# TimerShield.net
KiCad netlist of a schematic drawn in EAGLE
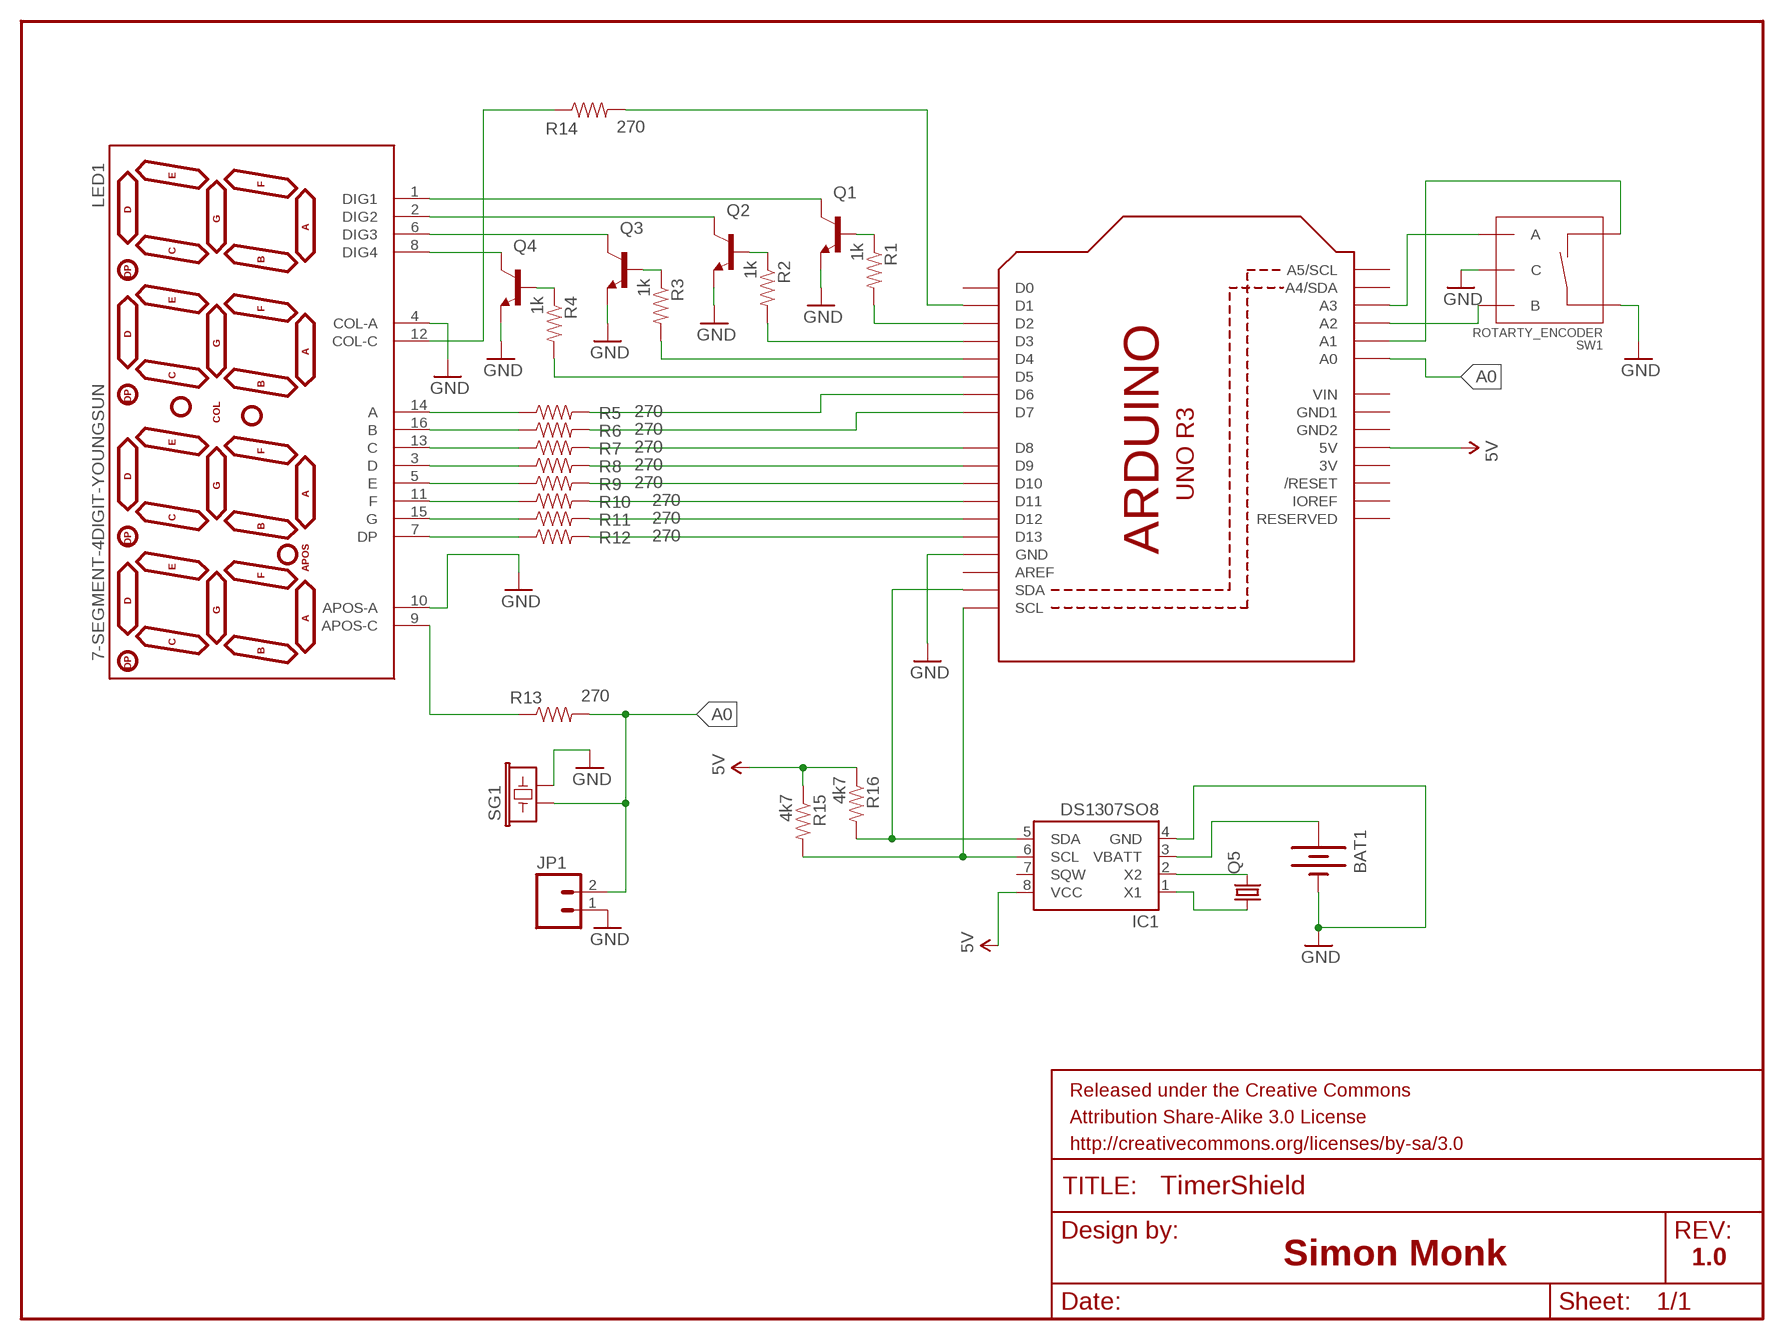
[diagram p0: schematic, sheet 1]

(export (version "E")
  (design (tool "Eeschema 10.0.6"))
  (components
    (comp (ref "BAT1")
      (value "BATTERY12MM")
      (footprint "eagle-import:BATTCON_12MM")
      (libsource (lib "eagle-import") (part "BATTERY12MM"))
    )
    (comp (ref "FRAME1")
      (value "FRAME-LETTER")
      (footprint "eagle-import:CREATIVE_COMMONS")
      (libsource (lib "eagle-import") (part "FRAME-LETTER"))
    )
    (comp (ref "IC1")
      (value "DS1307SO8")
      (footprint "eagle-import:SO08")
      (libsource (lib "eagle-import") (part "DS1307SO8"))
    )
    (comp (ref "JP1")
      (value "M023.5MM")
      (footprint "eagle-import:SCREWTERMINAL-3.5MM-2")
      (libsource (lib "eagle-import") (part "M023.5MM"))
    )
    (comp (ref "LED1")
      (value "7-SEGMENT-4DIGIT-YOUNGSUN")
      (footprint "eagle-import:7-SEGMENT-4DIGIT-YOUNGSUN")
      (libsource (lib "eagle-import") (part "7-SEGMENT-4DIGIT-YOUNGSUN"))
    )
    (comp (ref "Q1")
      (value "TRANSISTOR_NPNSOT23")
      (footprint "eagle-import:SOT23")
      (libsource (lib "eagle-import") (part "TRANSISTOR_NPNSOT23"))
    )
    (comp (ref "Q2")
      (value "TRANSISTOR_NPNSOT23")
      (footprint "eagle-import:SOT23")
      (libsource (lib "eagle-import") (part "TRANSISTOR_NPNSOT23"))
    )
    (comp (ref "Q3")
      (value "TRANSISTOR_NPNSOT23")
      (footprint "eagle-import:SOT23")
      (libsource (lib "eagle-import") (part "TRANSISTOR_NPNSOT23"))
    )
    (comp (ref "Q4")
      (value "TRANSISTOR_NPNSOT23")
      (footprint "eagle-import:SOT23")
      (libsource (lib "eagle-import") (part "TRANSISTOR_NPNSOT23"))
    )
    (comp (ref "Q5")
      (value "CRYSTALTC26H")
      (footprint "eagle-import:TC26H")
      (libsource (lib "eagle-import") (part "CRYSTALTC26H"))
    )
    (comp (ref "R1")
      (value "1k")
      (footprint "eagle-import:0805")
      (libsource (lib "eagle-import") (part "RESISTOR0805-RES"))
    )
    (comp (ref "R2")
      (value "1k")
      (footprint "eagle-import:0805")
      (libsource (lib "eagle-import") (part "RESISTOR0805-RES"))
    )
    (comp (ref "R3")
      (value "1k")
      (footprint "eagle-import:0805")
      (libsource (lib "eagle-import") (part "RESISTOR0805-RES"))
    )
    (comp (ref "R4")
      (value "1k")
      (footprint "eagle-import:0805")
      (libsource (lib "eagle-import") (part "RESISTOR0805-RES"))
    )
    (comp (ref "R5")
      (value "270")
      (footprint "eagle-import:0805")
      (libsource (lib "eagle-import") (part "RESISTOR0805-RES"))
    )
    (comp (ref "R6")
      (value "270")
      (footprint "eagle-import:0805")
      (libsource (lib "eagle-import") (part "RESISTOR0805-RES"))
    )
    (comp (ref "R7")
      (value "270")
      (footprint "eagle-import:0805")
      (libsource (lib "eagle-import") (part "RESISTOR0805-RES"))
    )
    (comp (ref "R8")
      (value "270")
      (footprint "eagle-import:0805")
      (libsource (lib "eagle-import") (part "RESISTOR0805-RES"))
    )
    (comp (ref "R9")
      (value "270")
      (footprint "eagle-import:0805")
      (libsource (lib "eagle-import") (part "RESISTOR0805-RES"))
    )
    (comp (ref "R10")
      (value "270")
      (footprint "eagle-import:0805")
      (libsource (lib "eagle-import") (part "RESISTOR0805-RES"))
    )
    (comp (ref "R11")
      (value "270")
      (footprint "eagle-import:0805")
      (libsource (lib "eagle-import") (part "RESISTOR0805-RES"))
    )
    (comp (ref "R12")
      (value "270")
      (footprint "eagle-import:0805")
      (libsource (lib "eagle-import") (part "RESISTOR0805-RES"))
    )
    (comp (ref "R13")
      (value "270")
      (footprint "eagle-import:0805")
      (libsource (lib "eagle-import") (part "RESISTOR0805-RES"))
    )
    (comp (ref "R14")
      (value "270")
      (footprint "eagle-import:0805")
      (libsource (lib "eagle-import") (part "RESISTOR0805-RES"))
    )
    (comp (ref "R15")
      (value "4k7")
      (footprint "eagle-import:0805")
      (libsource (lib "eagle-import") (part "RESISTOR0805-RES"))
    )
    (comp (ref "R16")
      (value "4k7")
      (footprint "eagle-import:0805")
      (libsource (lib "eagle-import") (part "RESISTOR0805-RES"))
    )
    (comp (ref "SG1")
      (value "BUZZERNS")
      (footprint "eagle-import:BUZZER-12MM-NS")
      (libsource (lib "eagle-import") (part "BUZZERNS"))
    )
    (comp (ref "SW1")
      (value "ROTARTY_ENCODER")
      (footprint "eagle-import:ROTARY_ENC_PLAIN")
      (libsource (lib "eagle-import") (part "ROTARTY_ENCODER"))
    )
    (comp (ref "U1")
      (value "ARDUINOR3-DIMENSION")
      (footprint "eagle-import:ARDUINOR3")
      (libsource (lib "eagle-import") (part "ARDUINOR3-DIMENSION"))
    )
  )
  (nets
    (net (code "1") (name "/3V") (class "Default")
      (node (ref "U1") (pin "3V") (pinfunction "3V_3V") (pintype "power_in"))
    )
    (net (code "2") (name "/GND1") (class "Default")
      (node (ref "U1") (pin "GND1") (pinfunction "GND1_GND1") (pintype "power_in"))
    )
    (net (code "3") (name "/GND2") (class "Default")
      (node (ref "U1") (pin "GND2") (pinfunction "GND2_GND2") (pintype "power_in"))
    )
    (net (code "4") (name "/VIN") (class "Default")
      (node (ref "U1") (pin "VIN") (pinfunction "VIN_VIN") (pintype "power_in"))
    )
    (net (code "5") (name "5V") (class "Default")
      (node (ref "IC1") (pin "8") (pinfunction "VCC_8") (pintype "bidirectional"))
      (node (ref "R15") (pin "1") (pinfunction "1_1") (pintype "passive"))
      (node (ref "R16") (pin "1") (pinfunction "1_1") (pintype "passive"))
      (node (ref "U1") (pin "5V") (pinfunction "5V_5V") (pintype "power_in"))
    )
    (net (code "6") (name "A0") (class "Default")
      (node (ref "JP1") (pin "2") (pinfunction "2_2") (pintype "passive"))
      (node (ref "R13") (pin "2") (pinfunction "2_2") (pintype "passive"))
      (node (ref "SG1") (pin "+") (pinfunction "1_+") (pintype "passive"))
      (node (ref "U1") (pin "A0") (pinfunction "A0_A0") (pintype "bidirectional"))
    )
    (net (code "7") (name "GND") (class "Default")
      (node (ref "BAT1") (pin "GND") (pinfunction "-_GND") (pintype "power_in"))
      (node (ref "IC1") (pin "4") (pinfunction "GND_4") (pintype "bidirectional"))
      (node (ref "JP1") (pin "1") (pinfunction "1_1") (pintype "passive"))
      (node (ref "LED1") (pin "10") (pinfunction "APOS-A_10") (pintype "bidirectional"))
      (node (ref "LED1") (pin "4") (pinfunction "COL-A_4") (pintype "bidirectional"))
      (node (ref "Q1") (pin "2") (pinfunction "E_2") (pintype "passive"))
      (node (ref "Q2") (pin "2") (pinfunction "E_2") (pintype "passive"))
      (node (ref "Q3") (pin "2") (pinfunction "E_2") (pintype "passive"))
      (node (ref "Q4") (pin "2") (pinfunction "E_2") (pintype "passive"))
      (node (ref "SG1") (pin "-") (pinfunction "2_-") (pintype "passive"))
      (node (ref "SW1") (pin "C") (pinfunction "C_C") (pintype "bidirectional"))
      (node (ref "SW1") (pin "SW+") (pinfunction "SW+_SW+") (pintype "bidirectional"))
      (node (ref "U1") (pin "GND") (pinfunction "GND_GND") (pintype "power_in"))
    )
    (net (code "8") (name "Net-(BAT1-+)") (class "Default")
      (node (ref "BAT1") (pin "PWR@1") (pinfunction "+_PWR@1") (pintype "power_in"))
      (node (ref "IC1") (pin "3") (pinfunction "VBATT_3") (pintype "bidirectional"))
    )
    (net (code "9") (name "Net-(IC1-SCL)") (class "Default")
      (node (ref "IC1") (pin "6") (pinfunction "SCL_6") (pintype "bidirectional"))
      (node (ref "R15") (pin "2") (pinfunction "2_2") (pintype "passive"))
      (node (ref "U1") (pin "SCL") (pinfunction "SCL_SCL") (pintype "bidirectional"))
    )
    (net (code "10") (name "Net-(IC1-SDA)") (class "Default")
      (node (ref "IC1") (pin "5") (pinfunction "SDA_5") (pintype "bidirectional"))
      (node (ref "R16") (pin "2") (pinfunction "2_2") (pintype "passive"))
      (node (ref "U1") (pin "SDA") (pinfunction "SDA_SDA") (pintype "bidirectional"))
    )
    (net (code "11") (name "Net-(IC1-X1)") (class "Default")
      (node (ref "IC1") (pin "1") (pinfunction "X1_1") (pintype "bidirectional"))
      (node (ref "Q5") (pin "1") (pinfunction "1_1") (pintype "passive"))
    )
    (net (code "12") (name "Net-(IC1-X2)") (class "Default")
      (node (ref "IC1") (pin "2") (pinfunction "X2_2") (pintype "bidirectional"))
      (node (ref "Q5") (pin "2") (pinfunction "2_2") (pintype "passive"))
    )
    (net (code "13") (name "Net-(LED1-A)") (class "Default")
      (node (ref "LED1") (pin "14") (pinfunction "A_14") (pintype "bidirectional"))
      (node (ref "R5") (pin "1") (pinfunction "1_1") (pintype "passive"))
    )
    (net (code "14") (name "Net-(LED1-APOS-C)") (class "Default")
      (node (ref "LED1") (pin "9") (pinfunction "APOS-C_9") (pintype "bidirectional"))
      (node (ref "R13") (pin "1") (pinfunction "1_1") (pintype "passive"))
    )
    (net (code "15") (name "Net-(LED1-B)") (class "Default")
      (node (ref "LED1") (pin "16") (pinfunction "B_16") (pintype "bidirectional"))
      (node (ref "R6") (pin "1") (pinfunction "1_1") (pintype "passive"))
    )
    (net (code "16") (name "Net-(LED1-C)") (class "Default")
      (node (ref "LED1") (pin "13") (pinfunction "C_13") (pintype "bidirectional"))
      (node (ref "R7") (pin "1") (pinfunction "1_1") (pintype "passive"))
    )
    (net (code "17") (name "Net-(LED1-COL-C)") (class "Default")
      (node (ref "LED1") (pin "12") (pinfunction "COL-C_12") (pintype "bidirectional"))
      (node (ref "R14") (pin "1") (pinfunction "1_1") (pintype "passive"))
    )
    (net (code "18") (name "Net-(LED1-D)") (class "Default")
      (node (ref "LED1") (pin "3") (pinfunction "D_3") (pintype "bidirectional"))
      (node (ref "R8") (pin "1") (pinfunction "1_1") (pintype "passive"))
    )
    (net (code "19") (name "Net-(LED1-DIG1)") (class "Default")
      (node (ref "LED1") (pin "1") (pinfunction "DIG1_1") (pintype "bidirectional"))
      (node (ref "Q1") (pin "3") (pinfunction "C_3") (pintype "passive"))
    )
    (net (code "20") (name "Net-(LED1-DIG2)") (class "Default")
      (node (ref "LED1") (pin "2") (pinfunction "DIG2_2") (pintype "bidirectional"))
      (node (ref "Q2") (pin "3") (pinfunction "C_3") (pintype "passive"))
    )
    (net (code "21") (name "Net-(LED1-DIG3)") (class "Default")
      (node (ref "LED1") (pin "6") (pinfunction "DIG3_6") (pintype "bidirectional"))
      (node (ref "Q3") (pin "3") (pinfunction "C_3") (pintype "passive"))
    )
    (net (code "22") (name "Net-(LED1-DIG4)") (class "Default")
      (node (ref "LED1") (pin "8") (pinfunction "DIG4_8") (pintype "bidirectional"))
      (node (ref "Q4") (pin "3") (pinfunction "C_3") (pintype "passive"))
    )
    (net (code "23") (name "Net-(LED1-DP)") (class "Default")
      (node (ref "LED1") (pin "7") (pinfunction "DP_7") (pintype "bidirectional"))
      (node (ref "R12") (pin "1") (pinfunction "1_1") (pintype "passive"))
    )
    (net (code "24") (name "Net-(LED1-E)") (class "Default")
      (node (ref "LED1") (pin "5") (pinfunction "E_5") (pintype "bidirectional"))
      (node (ref "R9") (pin "1") (pinfunction "1_1") (pintype "passive"))
    )
    (net (code "25") (name "Net-(LED1-F)") (class "Default")
      (node (ref "LED1") (pin "11") (pinfunction "F_11") (pintype "bidirectional"))
      (node (ref "R10") (pin "1") (pinfunction "1_1") (pintype "passive"))
    )
    (net (code "26") (name "Net-(LED1-G)") (class "Default")
      (node (ref "LED1") (pin "15") (pinfunction "G_15") (pintype "bidirectional"))
      (node (ref "R11") (pin "1") (pinfunction "1_1") (pintype "passive"))
    )
    (net (code "27") (name "Net-(Q1-B)") (class "Default")
      (node (ref "Q1") (pin "1") (pinfunction "B_1") (pintype "passive"))
      (node (ref "R1") (pin "1") (pinfunction "1_1") (pintype "passive"))
    )
    (net (code "28") (name "Net-(Q2-B)") (class "Default")
      (node (ref "Q2") (pin "1") (pinfunction "B_1") (pintype "passive"))
      (node (ref "R2") (pin "1") (pinfunction "1_1") (pintype "passive"))
    )
    (net (code "29") (name "Net-(Q3-B)") (class "Default")
      (node (ref "Q3") (pin "1") (pinfunction "B_1") (pintype "passive"))
      (node (ref "R3") (pin "1") (pinfunction "1_1") (pintype "passive"))
    )
    (net (code "30") (name "Net-(Q4-B)") (class "Default")
      (node (ref "Q4") (pin "1") (pinfunction "B_1") (pintype "passive"))
      (node (ref "R4") (pin "1") (pinfunction "1_1") (pintype "passive"))
    )
    (net (code "31") (name "Net-(R1-Pad2)") (class "Default")
      (node (ref "R1") (pin "2") (pinfunction "2_2") (pintype "passive"))
      (node (ref "U1") (pin "D2") (pinfunction "D2_D2") (pintype "bidirectional"))
    )
    (net (code "32") (name "Net-(R2-Pad2)") (class "Default")
      (node (ref "R2") (pin "2") (pinfunction "2_2") (pintype "passive"))
      (node (ref "U1") (pin "D3") (pinfunction "D3_D3") (pintype "bidirectional"))
    )
    (net (code "33") (name "Net-(R3-Pad2)") (class "Default")
      (node (ref "R3") (pin "2") (pinfunction "2_2") (pintype "passive"))
      (node (ref "U1") (pin "D4") (pinfunction "D4_D4") (pintype "bidirectional"))
    )
    (net (code "34") (name "Net-(R4-Pad2)") (class "Default")
      (node (ref "R4") (pin "2") (pinfunction "2_2") (pintype "passive"))
      (node (ref "U1") (pin "D5") (pinfunction "D5_D5") (pintype "bidirectional"))
    )
    (net (code "35") (name "Net-(R5-Pad2)") (class "Default")
      (node (ref "R5") (pin "2") (pinfunction "2_2") (pintype "passive"))
      (node (ref "U1") (pin "D6") (pinfunction "D6_D6") (pintype "bidirectional"))
    )
    (net (code "36") (name "Net-(R6-Pad2)") (class "Default")
      (node (ref "R6") (pin "2") (pinfunction "2_2") (pintype "passive"))
      (node (ref "U1") (pin "D7") (pinfunction "D7_D7") (pintype "bidirectional"))
    )
    (net (code "37") (name "Net-(R7-Pad2)") (class "Default")
      (node (ref "R7") (pin "2") (pinfunction "2_2") (pintype "passive"))
      (node (ref "U1") (pin "D8") (pinfunction "D8_D8") (pintype "bidirectional"))
    )
    (net (code "38") (name "Net-(R8-Pad2)") (class "Default")
      (node (ref "R8") (pin "2") (pinfunction "2_2") (pintype "passive"))
      (node (ref "U1") (pin "D9") (pinfunction "D9_D9") (pintype "bidirectional"))
    )
    (net (code "39") (name "Net-(R9-Pad2)") (class "Default")
      (node (ref "R9") (pin "2") (pinfunction "2_2") (pintype "passive"))
      (node (ref "U1") (pin "D10") (pinfunction "D10_D10") (pintype "bidirectional"))
    )
    (net (code "40") (name "Net-(R10-Pad2)") (class "Default")
      (node (ref "R10") (pin "2") (pinfunction "2_2") (pintype "passive"))
      (node (ref "U1") (pin "D11") (pinfunction "D11_D11") (pintype "bidirectional"))
    )
    (net (code "41") (name "Net-(R11-Pad2)") (class "Default")
      (node (ref "R11") (pin "2") (pinfunction "2_2") (pintype "passive"))
      (node (ref "U1") (pin "D12") (pinfunction "D12_D12") (pintype "bidirectional"))
    )
    (net (code "42") (name "Net-(R12-Pad2)") (class "Default")
      (node (ref "R12") (pin "2") (pinfunction "2_2") (pintype "passive"))
      (node (ref "U1") (pin "D13") (pinfunction "D13_D13") (pintype "bidirectional"))
    )
    (net (code "43") (name "Net-(R14-Pad2)") (class "Default")
      (node (ref "R14") (pin "2") (pinfunction "2_2") (pintype "passive"))
      (node (ref "U1") (pin "D1") (pinfunction "D1_D1") (pintype "bidirectional"))
    )
    (net (code "44") (name "Net-(SW1-PadA)") (class "Default")
      (node (ref "SW1") (pin "A") (pinfunction "A_A") (pintype "bidirectional"))
      (node (ref "U1") (pin "A3") (pinfunction "A3_A3") (pintype "bidirectional"))
    )
    (net (code "45") (name "Net-(SW1-PadB)") (class "Default")
      (node (ref "SW1") (pin "B") (pinfunction "B_B") (pintype "bidirectional"))
      (node (ref "U1") (pin "A2") (pinfunction "A2_A2") (pintype "bidirectional"))
    )
    (net (code "46") (name "Net-(SW1-PadSW-)") (class "Default")
      (node (ref "SW1") (pin "SW-") (pinfunction "SW-_SW-") (pintype "bidirectional"))
      (node (ref "U1") (pin "A1") (pinfunction "A1_A1") (pintype "bidirectional"))
    )
    (net (code "47") (name "unconnected-(IC1-SQW-Pad7)") (class "Default")
      (node (ref "IC1") (pin "7") (pinfunction "SQW_7") (pintype "bidirectional"))
    )
    (net (code "48") (name "unconnected-(U1-A4{slash}SDA-PadA4)") (class "Default")
      (node (ref "U1") (pin "A4") (pinfunction "A4/SDA_A4") (pintype "bidirectional"))
    )
    (net (code "49") (name "unconnected-(U1-A5{slash}SCL-PadA5)") (class "Default")
      (node (ref "U1") (pin "A5") (pinfunction "A5/SCL_A5") (pintype "bidirectional"))
    )
    (net (code "50") (name "unconnected-(U1-PadAREF)") (class "Default")
      (node (ref "U1") (pin "AREF") (pinfunction "AREF_AREF") (pintype "bidirectional"))
    )
    (net (code "51") (name "unconnected-(U1-PadD0)") (class "Default")
      (node (ref "U1") (pin "D0") (pinfunction "D0_D0") (pintype "bidirectional"))
    )
    (net (code "52") (name "unconnected-(U1-PadIOREF)") (class "Default")
      (node (ref "U1") (pin "IOREF") (pinfunction "IOREF_IOREF") (pintype "output"))
    )
    (net (code "53") (name "unconnected-(U1-PadRESERVED)") (class "Default")
      (node (ref "U1") (pin "RESERVED") (pinfunction "RESERVED_RESERVED") (pintype "no_connect"))
    )
    (net (code "54") (name "unconnected-(U1-{slash}RESET-PadRESET)") (class "Default")
      (node (ref "U1") (pin "RESET") (pinfunction "/RESET_RESET") (pintype "bidirectional"))
    )
  )
)
